# ClosedLoop_Drive_MC_MicroSD_Card.net
KiCad netlist of a schematic drawn in Altium Designer
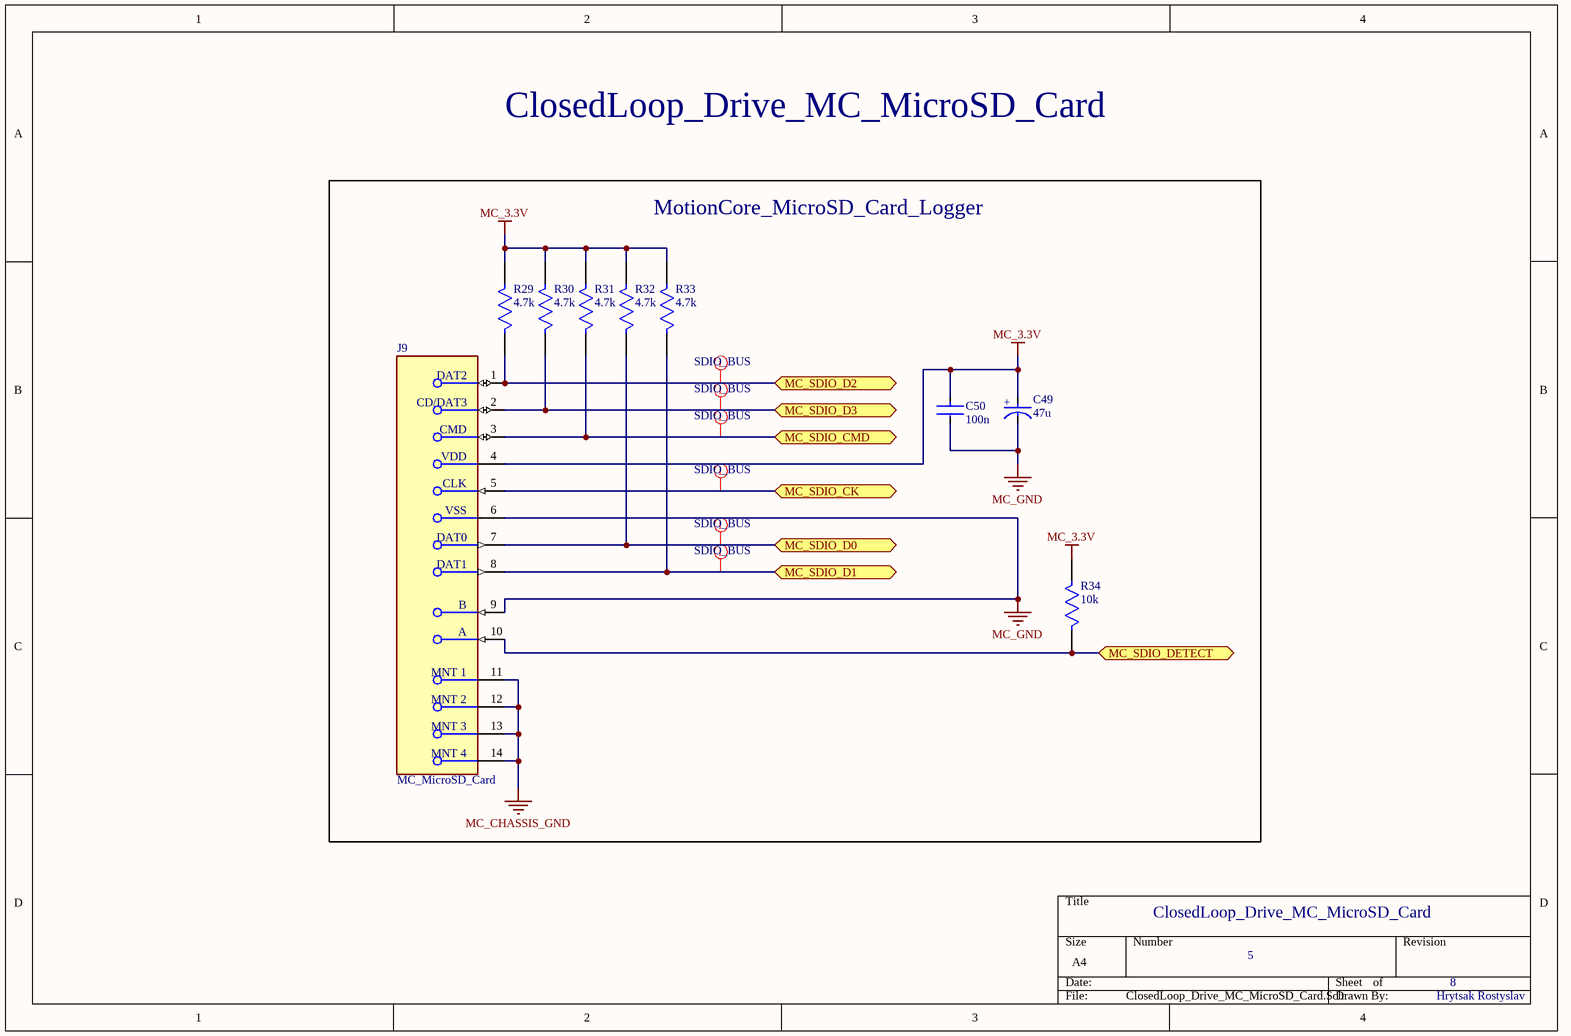
[diagram p0: ClosedLoop_Drive_MC_MicroSD_Card.SchDoc]

(export (version "E")
  (design (tool "Eeschema 10.0.6"))
  (components
    (comp (ref "C49")
      (value "47u")
      (footprint "FP-RAD-TH-D_6_3_0_5-L_11-MFG")
      (description "Aluminum Electrolytic Capacitors (Radial Lead Type) AEC-Q200 Qualified 100uF ±20% 25V")
      (fields (field (name "TOLERANCE") "20%"))
      (libsource (lib "Altium Content Vault") (part "203bc49f2ac43e59fd269a8c329ed05"))
    )
    (comp (ref "C50")
      (value "100n")
      (footprint "FP-0805-L_2_01_0_2-W_1_25-MFG")
      (description "0805")
      (fields (field (name "TOLERANCE") "10%"))
      (libsource (lib "Altium Content Vault") (part "b4654b650e69147ec39a6b967a45e02"))
    )
    (comp (ref "J9")
      (value "MC_MicroSD_Card")
      (footprint "FP-DM3AT-SF-PEJM5_40-MFG")
      (description "CONN MICRO SD R/A PUSH-PUSH SMD")
      (libsource (lib "Altium Content Vault") (part "363a2d875a73abe4217ddf3c28cd004"))
    )
    (comp (ref "R29")
      (value "4.7k")
      (footprint "FP-MCU0805-IPC_A")
      (description "0805")
      (fields (field (name "TOLERANCE") "0.5%"))
      (libsource (lib "Altium Content Vault") (part "1029c3af85768c4190bb7ad29bc67b5"))
    )
    (comp (ref "R30")
      (value "4.7k")
      (footprint "FP-MCU0805-IPC_A")
      (description "0805")
      (fields (field (name "TOLERANCE") "0.5%"))
      (libsource (lib "Altium Content Vault") (part "1029c3af85768c4190bb7ad29bc67b5"))
    )
    (comp (ref "R31")
      (value "4.7k")
      (footprint "FP-MCU0805-IPC_A")
      (description "0805")
      (fields (field (name "TOLERANCE") "0.5%"))
      (libsource (lib "Altium Content Vault") (part "1029c3af85768c4190bb7ad29bc67b5"))
    )
    (comp (ref "R32")
      (value "4.7k")
      (footprint "FP-MCU0805-IPC_A")
      (description "0805")
      (fields (field (name "TOLERANCE") "0.5%"))
      (libsource (lib "Altium Content Vault") (part "1029c3af85768c4190bb7ad29bc67b5"))
    )
    (comp (ref "R33")
      (value "4.7k")
      (footprint "FP-MCU0805-IPC_A")
      (description "0805")
      (fields (field (name "TOLERANCE") "0.5%"))
      (libsource (lib "Altium Content Vault") (part "1029c3af85768c4190bb7ad29bc67b5"))
    )
    (comp (ref "R34")
      (value "10k")
      (footprint "FP-MCU0805-IPC_A")
      (description "0805")
      (fields (field (name "TOLERANCE") "0.5%"))
      (libsource (lib "Altium Content Vault") (part "1029c3af85768c4190bb7ad29bc67b5"))
    )
  )
  (nets
    (net (code "1") (name "/MC_SDIO_CK") (class "Default")
      (node (ref "J9") (pin "5") (pinfunction "CLK_5") (pintype "input"))
    )
    (net (code "2") (name "/MC_SDIO_CMD") (class "Default")
      (node (ref "J9") (pin "3") (pinfunction "CMD_3") (pintype "bidirectional"))
      (node (ref "R31") (pin "1") (pinfunction "1_1") (pintype "passive"))
    )
    (net (code "3") (name "/MC_SDIO_D0") (class "Default")
      (node (ref "J9") (pin "7") (pinfunction "DAT0_7") (pintype "output"))
      (node (ref "R32") (pin "1") (pinfunction "1_1") (pintype "passive"))
    )
    (net (code "4") (name "/MC_SDIO_D1") (class "Default")
      (node (ref "J9") (pin "8") (pinfunction "DAT1_8") (pintype "output"))
      (node (ref "R33") (pin "1") (pinfunction "1_1") (pintype "passive"))
    )
    (net (code "5") (name "/MC_SDIO_D2") (class "Default")
      (node (ref "J9") (pin "1") (pinfunction "DAT2_1") (pintype "bidirectional"))
      (node (ref "R29") (pin "1") (pinfunction "1_1") (pintype "passive"))
    )
    (net (code "6") (name "/MC_SDIO_D3") (class "Default")
      (node (ref "J9") (pin "2") (pinfunction "CD/DAT3_2") (pintype "bidirectional"))
      (node (ref "R30") (pin "1") (pinfunction "1_1") (pintype "passive"))
    )
    (net (code "7") (name "/MC_SDIO_DETECT") (class "Default")
      (node (ref "J9") (pin "10") (pinfunction "A_10") (pintype "input"))
      (node (ref "R34") (pin "1") (pinfunction "1_1") (pintype "passive"))
    )
    (net (code "8") (name "MC_3.3V") (class "Default")
      (node (ref "C49") (pin "2") (pinfunction "A_2") (pintype "passive"))
      (node (ref "C50") (pin "1") (pinfunction "1_1") (pintype "passive"))
      (node (ref "J9") (pin "4") (pinfunction "VDD_4") (pintype "power_in"))
      (node (ref "R29") (pin "2") (pinfunction "2_2") (pintype "passive"))
      (node (ref "R30") (pin "2") (pinfunction "2_2") (pintype "passive"))
      (node (ref "R31") (pin "2") (pinfunction "2_2") (pintype "passive"))
      (node (ref "R32") (pin "2") (pinfunction "2_2") (pintype "passive"))
      (node (ref "R33") (pin "2") (pinfunction "2_2") (pintype "passive"))
      (node (ref "R34") (pin "2") (pinfunction "2_2") (pintype "passive"))
    )
    (net (code "9") (name "MC_CHASSIS_GND") (class "Default")
      (node (ref "J9") (pin "11") (pinfunction "MNT_1_11") (pintype "passive"))
      (node (ref "J9") (pin "12") (pinfunction "MNT_2_12") (pintype "passive"))
      (node (ref "J9") (pin "13") (pinfunction "MNT_3_13") (pintype "passive"))
      (node (ref "J9") (pin "14") (pinfunction "MNT_4_14") (pintype "passive"))
    )
    (net (code "10") (name "MC_GND") (class "Default")
      (node (ref "C49") (pin "1") (pinfunction "C_1") (pintype "passive"))
      (node (ref "C50") (pin "2") (pinfunction "2_2") (pintype "passive"))
      (node (ref "J9") (pin "6") (pinfunction "VSS_6") (pintype "passive"))
      (node (ref "J9") (pin "9") (pinfunction "B_9") (pintype "input"))
    )
  )
)
